# FPGA.net
KiCad netlist of a schematic drawn in Altium Designer
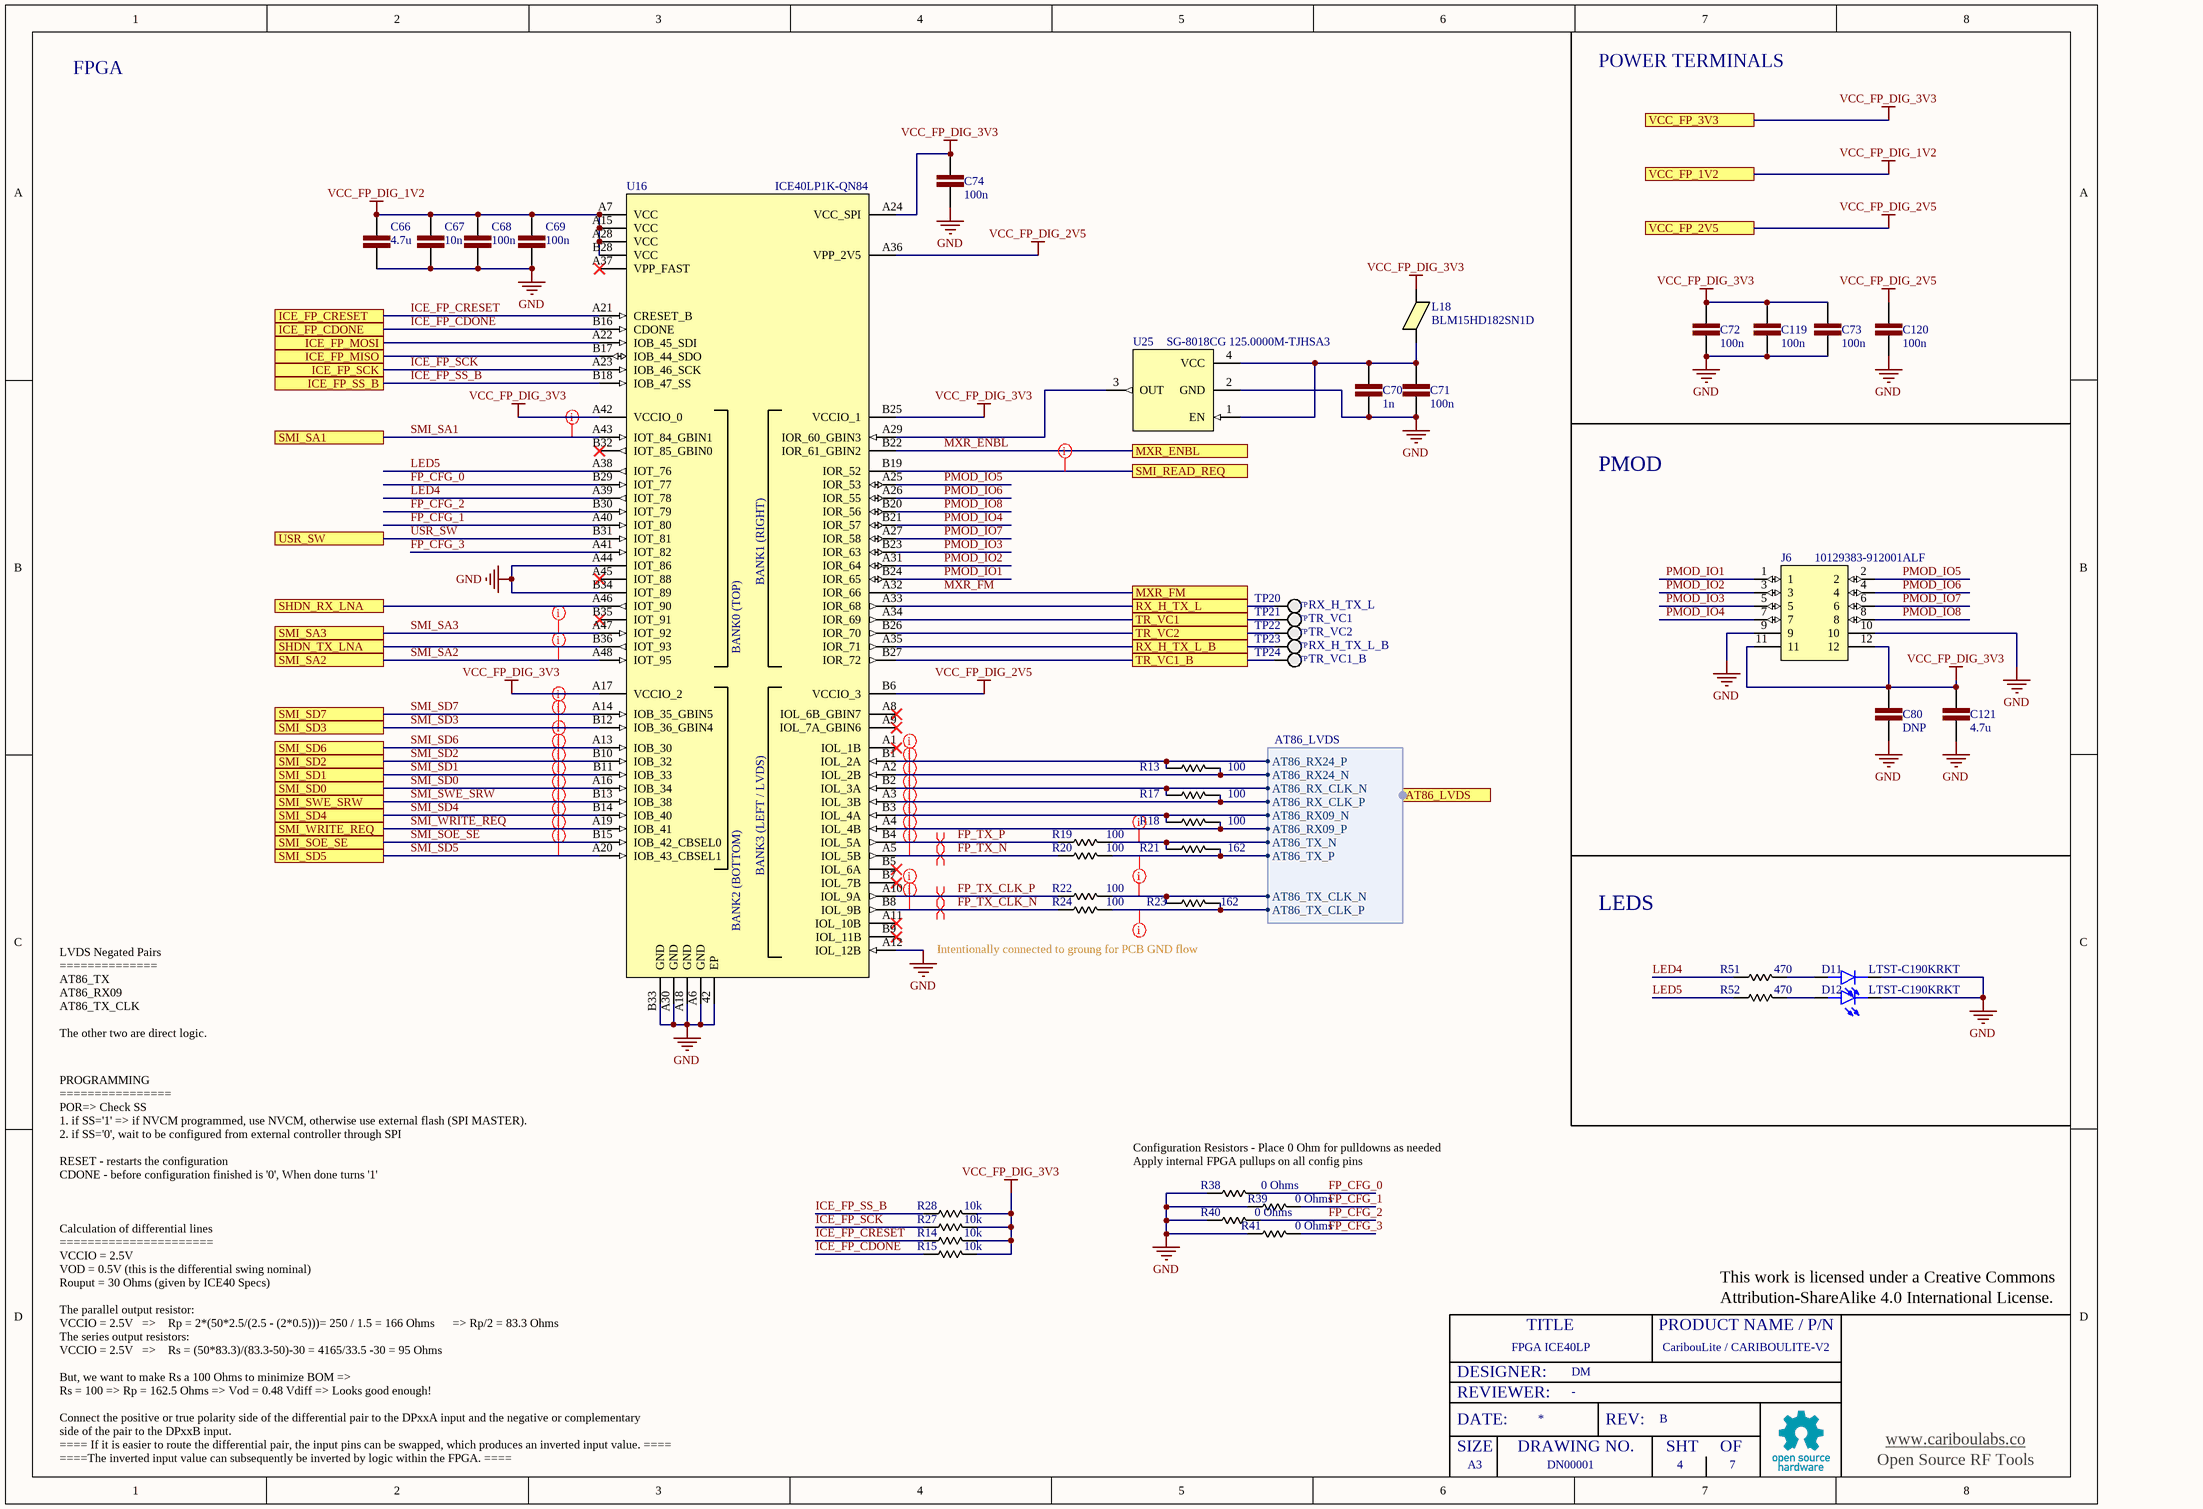
[diagram p0: FPGA.SchDoc]

(export (version "E")
  (design (tool "Eeschema 10.0.6"))
  (components
    (comp (ref "C66")
      (value "4.7u")
      (footprint "MURATA 0402")
      (description "Multilayer Ceramic Capacitors MLCC - SMD/SMT 0402 MLCC X5R 4.7 uF +/ -20% 10V")
      (fields (field (name "TOLERANCE") "20%"))
      (libsource (lib "CuSiP_Lib") (part "Capacitor"))
    )
    (comp (ref "C67")
      (value "10n")
      (footprint "MURATA 0402")
      (description "Multilayer Ceramic Capacitors MLCC - SMD/SMT 0402, 0.01UF 25V C0G")
      (fields (field (name "TOLERANCE") "5%"))
      (libsource (lib "CuSiP_Lib") (part "Capacitor"))
    )
    (comp (ref "C68")
      (value "100n")
      (footprint "MURATA 0402")
      (description "Multilayer Ceramic Capacitors MLCC - SMD/SMT 16V .1uF X5R 0402 10%")
      (fields (field (name "TOLERANCE") "10%"))
      (libsource (lib "") (part "Capacitor_1"))
    )
    (comp (ref "C69")
      (value "100n")
      (footprint "MURATA 0402")
      (description "Multilayer Ceramic Capacitors MLCC - SMD/SMT 16V .1uF X5R 0402 10%")
      (fields (field (name "TOLERANCE") "10%"))
      (libsource (lib "") (part "Capacitor_1"))
    )
    (comp (ref "C70")
      (value "1n")
      (footprint "MURATA 0402")
      (description "Multilayer Ceramic Capacitors MLCC 1000pF ±5% 100V C0G 0402")
      (fields (field (name "TOLERANCE") "5%"))
      (libsource (lib "") (part "Capacitor_2"))
    )
    (comp (ref "C71")
      (value "100n")
      (footprint "MURATA 0402")
      (description "Multilayer Ceramic Capacitors MLCC - SMD/SMT 16V .1uF X5R 0402 10%")
      (fields (field (name "TOLERANCE") "10%"))
      (libsource (lib "") (part "Capacitor_2"))
    )
    (comp (ref "C72")
      (value "100n")
      (footprint "MURATA 0402")
      (description "Multilayer Ceramic Capacitors MLCC - SMD/SMT 16V .1uF X5R 0402 10%")
      (fields (field (name "TOLERANCE") "10%"))
      (libsource (lib "CuSiP_Lib") (part "Capacitor"))
    )
    (comp (ref "C73")
      (value "100n")
      (footprint "MURATA 0402")
      (description "Multilayer Ceramic Capacitors MLCC - SMD/SMT 16V .1uF X5R 0402 10%")
      (fields (field (name "TOLERANCE") "10%"))
      (libsource (lib "") (part "Capacitor_1"))
    )
    (comp (ref "C74")
      (value "100n")
      (footprint "MURATA 0402")
      (description "Multilayer Ceramic Capacitors MLCC - SMD/SMT 16V .1uF X5R 0402 10%")
      (fields (field (name "TOLERANCE") "10%"))
      (libsource (lib "") (part "Capacitor_1"))
    )
    (comp (ref "C80")
      (value "DNP")
      (footprint "MURATA 0402")
      (description "Multilayer Ceramic Capacitors MLCC - SMD/SMT 0402 MLCC X5R 4.7 uF +/ -20% 10V")
      (fields (field (name "TOLERANCE") "20%"))
      (libsource (lib "CuSiP_Lib") (part "Capacitor"))
    )
    (comp (ref "C119")
      (value "100n")
      (footprint "MURATA 0402")
      (description "Multilayer Ceramic Capacitors MLCC - SMD/SMT 16V .1uF X5R 0402 10%")
      (fields (field (name "TOLERANCE") "10%"))
      (libsource (lib "CuSiP_Lib") (part "Capacitor"))
    )
    (comp (ref "C120")
      (value "100n")
      (footprint "MURATA 0402")
      (description "Multilayer Ceramic Capacitors MLCC - SMD/SMT 16V .1uF X5R 0402 10%")
      (fields (field (name "TOLERANCE") "10%"))
      (libsource (lib "") (part "Capacitor_1"))
    )
    (comp (ref "C121")
      (value "4.7u")
      (footprint "MURATA 0402")
      (description "Multilayer Ceramic Capacitors MLCC - SMD/SMT 0402 MLCC X5R 4.7 uF +/ -20% 10V")
      (fields (field (name "TOLERANCE") "20%"))
      (libsource (lib "CuSiP_Lib") (part "Capacitor"))
    )
    (comp (ref "D11")
      (value "LTST-C190KRKT")
      (footprint "LEDC1608X35N")
      (description "Red 631nm LED Indication - Discrete 2V 0603")
      (fields (field (name "MANU. P/N") "LTST-C190KRKT"))
      (libsource (lib "CuSiP_Lib") (part "LTST-C190KRKT"))
    )
    (comp (ref "D12")
      (value "LTST-C190KRKT")
      (footprint "LEDC1608X35N")
      (description "Red 631nm LED Indication - Discrete 2V 0603")
      (fields (field (name "MANU. P/N") "LTST-C190KRKT"))
      (libsource (lib "CuSiP_Lib") (part "LTST-C190KRKT"))
    )
    (comp (ref "J6")
      (value "10129383-912001ALF")
      (footprint "10129383912001ALF")
      (description "Headers & Wire Housings ECONOSTIK HEADER DR VT SMT 2X6")
      (fields (field (name "MANU. P/N") "10129383-912001ALF"))
      (libsource (lib "CuSiP_Lib") (part "10129383-912001ALF"))
    )
    (comp (ref "L18")
      (value "BLM15HD182SN1D")
      (footprint "0402 FERRITE BEAD")
      (description "Ferrite Beads 1800ohms GHz HiSpd")
      (fields (field (name "TOLERANCE") "25%") (field (name "MANU. P/N") "BLM15HD182SN1D"))
      (libsource (lib "CuSiP_Lib") (part "BLM15"))
    )
    (comp (ref "R13")
      (value "100")
      (footprint "PANASONIC 0402")
      (description "Thick Film Resistors - SMD 1/16watt 100ohms 1%")
      (fields (field (name "TOLERANCE") "1%"))
      (libsource (lib "CuSiP_Lib") (part "Resistor"))
    )
    (comp (ref "R14")
      (value "10k")
      (footprint "PANASONIC 0402")
      (description "Thick Film Resistors - SMD 0402 1/16watt 10Kohms 1%")
      (fields (field (name "TOLERANCE") "1%"))
      (libsource (lib "CuSiP_Lib") (part "Resistor"))
    )
    (comp (ref "R15")
      (value "10k")
      (footprint "PANASONIC 0402")
      (description "Thick Film Resistors - SMD 0402 1/16watt 10Kohms 1%")
      (fields (field (name "TOLERANCE") "1%"))
      (libsource (lib "CuSiP_Lib") (part "Resistor"))
    )
    (comp (ref "R17")
      (value "100")
      (footprint "PANASONIC 0402")
      (description "Thick Film Resistors - SMD 1/16watt 100ohms 1%")
      (fields (field (name "TOLERANCE") "1%"))
      (libsource (lib "CuSiP_Lib") (part "Resistor"))
    )
    (comp (ref "R18")
      (value "100")
      (footprint "PANASONIC 0402")
      (description "Thick Film Resistors - SMD 1/16watt 100ohms 1%")
      (fields (field (name "TOLERANCE") "1%"))
      (libsource (lib "CuSiP_Lib") (part "Resistor"))
    )
    (comp (ref "R19")
      (value "100")
      (footprint "PANASONIC 0402")
      (description "Thick Film Resistors - SMD 1/16watt 100ohms 1%")
      (fields (field (name "TOLERANCE") "1%"))
      (libsource (lib "CuSiP_Lib") (part "Resistor"))
    )
    (comp (ref "R20")
      (value "100")
      (footprint "PANASONIC 0402")
      (description "Thick Film Resistors - SMD 1/16watt 100ohms 1%")
      (fields (field (name "TOLERANCE") "1%"))
      (libsource (lib "CuSiP_Lib") (part "Resistor"))
    )
    (comp (ref "R21")
      (value "162")
      (footprint "PANASONIC 0402")
      (description "Thick Film Resistors - SMD 1/16watt 162ohms 1%")
      (fields (field (name "TOLERANCE") "1%"))
      (libsource (lib "CuSiP_Lib") (part "Resistor"))
    )
    (comp (ref "R22")
      (value "100")
      (footprint "PANASONIC 0402")
      (description "Thick Film Resistors - SMD 1/16watt 100ohms 1%")
      (fields (field (name "TOLERANCE") "1%"))
      (libsource (lib "CuSiP_Lib") (part "Resistor"))
    )
    (comp (ref "R23")
      (value "162")
      (footprint "PANASONIC 0402")
      (description "Thick Film Resistors - SMD 1/16watt 162ohms 1%")
      (fields (field (name "TOLERANCE") "1%"))
      (libsource (lib "CuSiP_Lib") (part "Resistor"))
    )
    (comp (ref "R24")
      (value "100")
      (footprint "PANASONIC 0402")
      (description "Thick Film Resistors - SMD 1/16watt 100ohms 1%")
      (fields (field (name "TOLERANCE") "1%"))
      (libsource (lib "CuSiP_Lib") (part "Resistor"))
    )
    (comp (ref "R27")
      (value "10k")
      (footprint "PANASONIC 0402")
      (description "Thick Film Resistors - SMD 0402 1/16watt 10Kohms 1%")
      (fields (field (name "TOLERANCE") "1%"))
      (libsource (lib "CuSiP_Lib") (part "Resistor"))
    )
    (comp (ref "R28")
      (value "10k")
      (footprint "PANASONIC 0402")
      (description "Thick Film Resistors - SMD 0402 1/16watt 10Kohms 1%")
      (fields (field (name "TOLERANCE") "1%"))
      (libsource (lib "CuSiP_Lib") (part "Resistor"))
    )
    (comp (ref "R38")
      (value "0 Ohms")
      (footprint "PANASONIC 0402")
      (description "Resistor")
      (fields (field (name "TOLERANCE") "1%"))
      (libsource (lib "") (part "Resistor_1"))
    )
    (comp (ref "R39")
      (value "0 Ohms")
      (footprint "PANASONIC 0402")
      (description "Resistor")
      (fields (field (name "TOLERANCE") "1%"))
      (libsource (lib "") (part "Resistor_1"))
    )
    (comp (ref "R40")
      (value "0 Ohms")
      (footprint "PANASONIC 0402")
      (description "Resistor")
      (fields (field (name "TOLERANCE") "1%"))
      (libsource (lib "") (part "Resistor_1"))
    )
    (comp (ref "R41")
      (value "0 Ohms")
      (footprint "PANASONIC 0402")
      (description "Resistor")
      (fields (field (name "TOLERANCE") "1%"))
      (libsource (lib "") (part "Resistor_1"))
    )
    (comp (ref "R51")
      (value "470")
      (footprint "PANASONIC 0402")
      (description "Thick Film Resistors - SMD 1/16watt 470ohms 1%")
      (fields (field (name "TOLERANCE") "1%"))
      (libsource (lib "CuSiP_Lib") (part "Resistor"))
    )
    (comp (ref "R52")
      (value "470")
      (footprint "PANASONIC 0402")
      (description "Thick Film Resistors - SMD 1/16watt 470ohms 1%")
      (fields (field (name "TOLERANCE") "1%"))
      (libsource (lib "CuSiP_Lib") (part "Resistor"))
    )
    (comp (ref "TP20")
      (value "RX_H_TX_L")
      (footprint "TP_40")
      (libsource (lib "CuSiP_Lib") (part "TEST_POINT"))
    )
    (comp (ref "TP21") (value "TR_VC1") (footprint "TP_40") (libsource (lib "CuSiP_Lib") (part "TEST_POINT")))
    (comp (ref "TP22") (value "TR_VC2") (footprint "TP_40") (libsource (lib "CuSiP_Lib") (part "TEST_POINT")))
    (comp (ref "TP23")
      (value "RX_H_TX_L_B")
      (footprint "TP_40")
      (libsource (lib "CuSiP_Lib") (part "TEST_POINT"))
    )
    (comp (ref "TP24")
      (value "TR_VC1_B")
      (footprint "TP_40")
      (libsource (lib "CuSiP_Lib") (part "TEST_POINT"))
    )
    (comp (ref "U16")
      (value "ICE40LP1K-QN84")
      (footprint "LATTICE_ICE40LP1K-QN84")
      (description "FPGA - Field Programmable Gate Array iCE40LP 1280 LUTs 1.2V Ultra Low-Power")
      (fields (field (name "MANU. P/N") "ICE40LP1K-QN84"))
      (libsource (lib "CuSiP_Lib") (part "ICE40LP1K-QN84"))
    )
    (comp (ref "U25")
      (value "SG-8018CG 125.0000M-TJHPA3")
      (footprint "SG-8018CG")
      (fields (field (name "MANU. P/N") "SG-8018CG 125.0000M-TJHSA3"))
      (libsource (lib "CuSiP_Lib") (part "SG-8018CG 125.0000M-TJHPA3"))
    )
  )
  (nets
    (net (code "2") (name "/FP_CFG_0") (class "Default")
      (node (ref "R38") (pin "1") (pinfunction "1_1") (pintype "passive"))
      (node (ref "U16") (pin "B29") (pinfunction "IOT_77_B29") (pintype "input"))
    )
    (net (code "3") (name "/FP_CFG_1") (class "Default")
      (node (ref "R39") (pin "1") (pinfunction "1_1") (pintype "passive"))
      (node (ref "U16") (pin "A40") (pinfunction "IOT_80_A40") (pintype "input"))
    )
    (net (code "4") (name "/FP_CFG_2") (class "Default")
      (node (ref "R40") (pin "1") (pinfunction "1_1") (pintype "passive"))
      (node (ref "U16") (pin "B30") (pinfunction "IOT_79_B30") (pintype "input"))
    )
    (net (code "5") (name "/FP_CFG_3") (class "Default")
      (node (ref "R41") (pin "1") (pinfunction "1_1") (pintype "passive"))
      (node (ref "U16") (pin "A41") (pinfunction "IOT_82_A41") (pintype "input"))
    )
    (net (code "6") (name "/FP_TX_CLK_N") (class "Default")
      (node (ref "R24") (pin "1") (pinfunction "1_1") (pintype "passive"))
      (node (ref "U16") (pin "B8") (pinfunction "IOL_9B_B8") (pintype "output"))
    )
    (net (code "7") (name "/FP_TX_CLK_P") (class "Default")
      (node (ref "R22") (pin "1") (pinfunction "1_1") (pintype "passive"))
      (node (ref "U16") (pin "A10") (pinfunction "IOL_9A_A10") (pintype "output"))
    )
    (net (code "8") (name "/FP_TX_N") (class "Default")
      (node (ref "R20") (pin "1") (pinfunction "1_1") (pintype "passive"))
      (node (ref "U16") (pin "A5") (pinfunction "IOL_5B_A5") (pintype "output"))
    )
    (net (code "9") (name "/FP_TX_P") (class "Default")
      (node (ref "R19") (pin "1") (pinfunction "1_1") (pintype "passive"))
      (node (ref "U16") (pin "B4") (pinfunction "IOL_5A_B4") (pintype "output"))
    )
    (net (code "10") (name "/ICE_FP_CDONE") (class "Default")
      (node (ref "R15") (pin "1") (pinfunction "1_1") (pintype "passive"))
      (node (ref "U16") (pin "B16") (pinfunction "CDONE_B16") (pintype "input"))
    )
    (net (code "11") (name "/ICE_FP_CRESET") (class "Default")
      (node (ref "R14") (pin "1") (pinfunction "1_1") (pintype "passive"))
      (node (ref "U16") (pin "A21") (pinfunction "CRESET_B_A21") (pintype "input"))
    )
    (net (code "12") (name "/ICE_FP_MISO") (class "Default")
      (node (ref "U16") (pin "B17") (pinfunction "IOB_44_SDO_B17") (pintype "bidirectional"))
    )
    (net (code "13") (name "/ICE_FP_MOSI") (class "Default")
      (node (ref "U16") (pin "A22") (pinfunction "IOB_45_SDI_A22") (pintype "input"))
    )
    (net (code "14") (name "/ICE_FP_SCK") (class "Default")
      (node (ref "R27") (pin "1") (pinfunction "1_1") (pintype "passive"))
      (node (ref "U16") (pin "A23") (pinfunction "IOB_46_SCK_A23") (pintype "input"))
    )
    (net (code "15") (name "/ICE_FP_SS_B") (class "Default")
      (node (ref "R28") (pin "1") (pinfunction "1_1") (pintype "passive"))
      (node (ref "U16") (pin "B18") (pinfunction "IOB_47_SS_B18") (pintype "input"))
    )
    (net (code "16") (name "/LED4") (class "Default")
      (node (ref "R51") (pin "1") (pinfunction "1_1") (pintype "passive"))
      (node (ref "U16") (pin "A39") (pinfunction "IOT_78_A39") (pintype "output"))
    )
    (net (code "17") (name "/LED5") (class "Default")
      (node (ref "R52") (pin "1") (pinfunction "1_1") (pintype "passive"))
      (node (ref "U16") (pin "A38") (pinfunction "IOT_76_A38") (pintype "output"))
    )
    (net (code "18") (name "/MXR_ENBL") (class "Default")
      (node (ref "U16") (pin "B22") (pinfunction "IOR_61_GBIN2_B22") (pintype "passive"))
    )
    (net (code "19") (name "/MXR_FM") (class "Default")
      (node (ref "U16") (pin "A32") (pinfunction "IOR_66_A32") (pintype "passive"))
    )
    (net (code "20") (name "/PMOD_IO1") (class "Default")
      (node (ref "J6") (pin "1") (pinfunction "1_1") (pintype "bidirectional"))
      (node (ref "U16") (pin "B24") (pinfunction "IOR_65_B24") (pintype "bidirectional"))
    )
    (net (code "21") (name "/PMOD_IO2") (class "Default")
      (node (ref "J6") (pin "3") (pinfunction "3_3") (pintype "bidirectional"))
      (node (ref "U16") (pin "A31") (pinfunction "IOR_64_A31") (pintype "bidirectional"))
    )
    (net (code "22") (name "/PMOD_IO3") (class "Default")
      (node (ref "J6") (pin "5") (pinfunction "5_5") (pintype "bidirectional"))
      (node (ref "U16") (pin "B23") (pinfunction "IOR_63_B23") (pintype "bidirectional"))
    )
    (net (code "23") (name "/PMOD_IO4") (class "Default")
      (node (ref "J6") (pin "7") (pinfunction "7_7") (pintype "bidirectional"))
      (node (ref "U16") (pin "B21") (pinfunction "IOR_57_B21") (pintype "bidirectional"))
    )
    (net (code "24") (name "/PMOD_IO5") (class "Default")
      (node (ref "J6") (pin "2") (pinfunction "2_2") (pintype "bidirectional"))
      (node (ref "U16") (pin "A25") (pinfunction "IOR_53_A25") (pintype "bidirectional"))
    )
    (net (code "25") (name "/PMOD_IO6") (class "Default")
      (node (ref "J6") (pin "4") (pinfunction "4_4") (pintype "bidirectional"))
      (node (ref "U16") (pin "A26") (pinfunction "IOR_55_A26") (pintype "bidirectional"))
    )
    (net (code "26") (name "/PMOD_IO7") (class "Default")
      (node (ref "J6") (pin "6") (pinfunction "6_6") (pintype "bidirectional"))
      (node (ref "U16") (pin "A27") (pinfunction "IOR_58_A27") (pintype "bidirectional"))
    )
    (net (code "27") (name "/PMOD_IO8") (class "Default")
      (node (ref "J6") (pin "8") (pinfunction "8_8") (pintype "bidirectional"))
      (node (ref "U16") (pin "B20") (pinfunction "IOR_56_B20") (pintype "bidirectional"))
    )
    (net (code "28") (name "/RX_H_TX_L") (class "Default")
      (node (ref "TP20") (pin "1") (pinfunction "TP_1") (pintype "passive"))
      (node (ref "U16") (pin "A33") (pinfunction "IOR_68_A33") (pintype "output"))
    )
    (net (code "29") (name "/RX_H_TX_L_B") (class "Default")
      (node (ref "TP23") (pin "1") (pinfunction "TP_1") (pintype "passive"))
      (node (ref "U16") (pin "A35") (pinfunction "IOR_71_A35") (pintype "output"))
    )
    (net (code "30") (name "/SHDN_RX_LNA") (class "Default")
      (node (ref "U16") (pin "A46") (pinfunction "IOT_90_A46") (pintype "output"))
    )
    (net (code "31") (name "/SHDN_TX_LNA") (class "Default")
      (node (ref "U16") (pin "B36") (pinfunction "IOT_93_B36") (pintype "output"))
    )
    (net (code "32") (name "/SMI_READ_REQ") (class "Default")
      (node (ref "U16") (pin "B19") (pinfunction "IOR_52_B19") (pintype "passive"))
    )
    (net (code "33") (name "/SMI_SA1") (class "Default")
      (node (ref "U16") (pin "A43") (pinfunction "IOT_84_GBIN1_A43") (pintype "input"))
    )
    (net (code "34") (name "/SMI_SA2") (class "Default")
      (node (ref "U16") (pin "A48") (pinfunction "IOT_95_A48") (pintype "input"))
    )
    (net (code "35") (name "/SMI_SA3") (class "Default")
      (node (ref "U16") (pin "A47") (pinfunction "IOT_92_A47") (pintype "input"))
    )
    (net (code "36") (name "/SMI_SD0") (class "Default")
      (node (ref "U16") (pin "A16") (pinfunction "IOB_34_A16") (pintype "input"))
    )
    (net (code "37") (name "/SMI_SD1") (class "Default")
      (node (ref "U16") (pin "B11") (pinfunction "IOB_33_B11") (pintype "input"))
    )
    (net (code "38") (name "/SMI_SD2") (class "Default")
      (node (ref "U16") (pin "B10") (pinfunction "IOB_32_B10") (pintype "input"))
    )
    (net (code "39") (name "/SMI_SD3") (class "Default")
      (node (ref "U16") (pin "B12") (pinfunction "IOB_36_GBIN4_B12") (pintype "input"))
    )
    (net (code "40") (name "/SMI_SD4") (class "Default")
      (node (ref "U16") (pin "B14") (pinfunction "IOB_40_B14") (pintype "input"))
    )
    (net (code "41") (name "/SMI_SD5") (class "Default")
      (node (ref "U16") (pin "A20") (pinfunction "IOB_43_CBSEL1_A20") (pintype "input"))
    )
    (net (code "42") (name "/SMI_SD6") (class "Default")
      (node (ref "U16") (pin "A13") (pinfunction "IOB_30_A13") (pintype "input"))
    )
    (net (code "43") (name "/SMI_SD7") (class "Default")
      (node (ref "U16") (pin "A14") (pinfunction "IOB_35_GBIN5_A14") (pintype "input"))
    )
    (net (code "44") (name "/SMI_SOE_SE") (class "Default")
      (node (ref "U16") (pin "B15") (pinfunction "IOB_42_CBSEL0_B15") (pintype "input"))
    )
    (net (code "45") (name "/SMI_SWE_SRW") (class "Default")
      (node (ref "U16") (pin "B13") (pinfunction "IOB_38_B13") (pintype "input"))
    )
    (net (code "46") (name "/SMI_WRITE_REQ") (class "Default")
      (node (ref "U16") (pin "A19") (pinfunction "IOB_41_A19") (pintype "input"))
    )
    (net (code "47") (name "/TR_VC1") (class "Default")
      (node (ref "TP21") (pin "1") (pinfunction "TP_1") (pintype "passive"))
      (node (ref "U16") (pin "A34") (pinfunction "IOR_69_A34") (pintype "output"))
    )
    (net (code "48") (name "/TR_VC1_B") (class "Default")
      (node (ref "TP24") (pin "1") (pinfunction "TP_1") (pintype "passive"))
      (node (ref "U16") (pin "B27") (pinfunction "IOR_72_B27") (pintype "output"))
    )
    (net (code "49") (name "/TR_VC2") (class "Default")
      (node (ref "TP22") (pin "1") (pinfunction "TP_1") (pintype "passive"))
      (node (ref "U16") (pin "B26") (pinfunction "IOR_70_B26") (pintype "output"))
    )
    (net (code "50") (name "/USR_SW") (class "Default")
      (node (ref "U16") (pin "B31") (pinfunction "IOT_81_B31") (pintype "input"))
    )
    (net (code "52") (name "GND") (class "Default")
      (node (ref "C119") (pin "2") (pinfunction "2_2") (pintype "passive"))
      (node (ref "C120") (pin "1") (pinfunction "1_1") (pintype "passive"))
      (node (ref "C121") (pin "2") (pinfunction "2_2") (pintype "passive"))
      (node (ref "C66") (pin "2") (pinfunction "2_2") (pintype "passive"))
      (node (ref "C67") (pin "2") (pinfunction "2_2") (pintype "passive"))
      (node (ref "C68") (pin "1") (pinfunction "1_1") (pintype "passive"))
      (node (ref "C69") (pin "1") (pinfunction "1_1") (pintype "passive"))
      (node (ref "C70") (pin "1") (pinfunction "1_1") (pintype "passive"))
      (node (ref "C71") (pin "1") (pinfunction "1_1") (pintype "passive"))
      (node (ref "C72") (pin "2") (pinfunction "2_2") (pintype "passive"))
      (node (ref "C73") (pin "1") (pinfunction "1_1") (pintype "passive"))
      (node (ref "C74") (pin "1") (pinfunction "1_1") (pintype "passive"))
      (node (ref "C80") (pin "2") (pinfunction "2_2") (pintype "passive"))
      (node (ref "D11") (pin "C") (pinfunction "C_C") (pintype "passive"))
      (node (ref "D12") (pin "C") (pinfunction "C_C") (pintype "passive"))
      (node (ref "J6") (pin "10") (pinfunction "10_10") (pintype "power_in"))
      (node (ref "J6") (pin "9") (pinfunction "9_9") (pintype "power_in"))
      (node (ref "R38") (pin "2") (pinfunction "2_2") (pintype "passive"))
      (node (ref "R39") (pin "2") (pinfunction "2_2") (pintype "passive"))
      (node (ref "R40") (pin "2") (pinfunction "2_2") (pintype "passive"))
      (node (ref "R41") (pin "2") (pinfunction "2_2") (pintype "passive"))
      (node (ref "U16") (pin "42") (pinfunction "EP_42") (pintype "power_in"))
      (node (ref "U16") (pin "A12") (pinfunction "IOL_12B_A12") (pintype "input"))
      (node (ref "U16") (pin "A18") (pinfunction "GND_A18") (pintype "power_in"))
      (node (ref "U16") (pin "A30") (pinfunction "GND_A30") (pintype "power_in"))
      (node (ref "U16") (pin "A44") (pinfunction "IOT_86_A44") (pintype "passive"))
      (node (ref "U16") (pin "A6") (pinfunction "GND_A6") (pintype "power_in"))
      (node (ref "U16") (pin "B33") (pinfunction "GND_B33") (pintype "power_in"))
      (node (ref "U16") (pin "B34") (pinfunction "IOT_89_B34") (pintype "passive"))
      (node (ref "U25") (pin "2") (pinfunction "GND_2") (pintype "power_in"))
    )
    (net (code "53") (name "Net-(D11-PadA)") (class "Default")
      (node (ref "D11") (pin "A") (pinfunction "A_A") (pintype "passive"))
      (node (ref "R51") (pin "2") (pinfunction "2_2") (pintype "passive"))
    )
    (net (code "54") (name "Net-(D12-PadA)") (class "Default")
      (node (ref "D12") (pin "A") (pinfunction "A_A") (pintype "passive"))
      (node (ref "R52") (pin "2") (pinfunction "2_2") (pintype "passive"))
    )
    (net (code "55") (name "Net-(R19-Pad2)") (class "Default")
      (node (ref "R19") (pin "2") (pinfunction "2_2") (pintype "passive"))
      (node (ref "R21") (pin "1") (pinfunction "1_1") (pintype "passive"))
    )
    (net (code "56") (name "Net-(R20-Pad2)") (class "Default")
      (node (ref "R20") (pin "2") (pinfunction "2_2") (pintype "passive"))
      (node (ref "R21") (pin "2") (pinfunction "2_2") (pintype "passive"))
    )
    (net (code "57") (name "Net-(R22-Pad2)") (class "Default")
      (node (ref "R22") (pin "2") (pinfunction "2_2") (pintype "passive"))
      (node (ref "R23") (pin "1") (pinfunction "1_1") (pintype "passive"))
    )
    (net (code "58") (name "Net-(R23-Pad2)") (class "Default")
      (node (ref "R23") (pin "2") (pinfunction "2_2") (pintype "passive"))
      (node (ref "R24") (pin "2") (pinfunction "2_2") (pintype "passive"))
    )
    (net (code "59") (name "Net-(U16-IOL_2A)") (class "Default")
      (node (ref "R13") (pin "1") (pinfunction "1_1") (pintype "passive"))
      (node (ref "U16") (pin "B1") (pinfunction "IOL_2A_B1") (pintype "input"))
    )
    (net (code "60") (name "Net-(U16-IOL_2B)") (class "Default")
      (node (ref "R13") (pin "2") (pinfunction "2_2") (pintype "passive"))
      (node (ref "U16") (pin "A2") (pinfunction "IOL_2B_A2") (pintype "input"))
    )
    (net (code "61") (name "Net-(U16-IOL_3A)") (class "Default")
      (node (ref "R17") (pin "1") (pinfunction "1_1") (pintype "passive"))
      (node (ref "U16") (pin "B2") (pinfunction "IOL_3A_B2") (pintype "input"))
    )
    (net (code "62") (name "Net-(U16-IOL_3B)") (class "Default")
      (node (ref "R17") (pin "2") (pinfunction "2_2") (pintype "passive"))
      (node (ref "U16") (pin "A3") (pinfunction "IOL_3B_A3") (pintype "input"))
    )
    (net (code "63") (name "Net-(U16-IOL_4A)") (class "Default")
      (node (ref "R18") (pin "1") (pinfunction "1_1") (pintype "passive"))
      (node (ref "U16") (pin "B3") (pinfunction "IOL_4A_B3") (pintype "input"))
    )
    (net (code "64") (name "Net-(U16-IOL_4B)") (class "Default")
      (node (ref "R18") (pin "2") (pinfunction "2_2") (pintype "passive"))
      (node (ref "U16") (pin "A4") (pinfunction "IOL_4B_A4") (pintype "input"))
    )
    (net (code "65") (name "Net-(U16-IOR_60_GBIN3)") (class "Default")
      (node (ref "U16") (pin "A29") (pinfunction "IOR_60_GBIN3_A29") (pintype "input"))
      (node (ref "U25") (pin "3") (pinfunction "OUT_3") (pintype "output"))
    )
    (net (code "66") (name "Net-(U25-EN)") (class "Default")
      (node (ref "C70") (pin "2") (pinfunction "2_2") (pintype "passive"))
      (node (ref "C71") (pin "2") (pinfunction "2_2") (pintype "passive"))
      (node (ref "L18") (pin "1") (pinfunction "1_1") (pintype "passive"))
      (node (ref "U25") (pin "1") (pinfunction "EN_1") (pintype "input"))
      (node (ref "U25") (pin "4") (pinfunction "VCC_4") (pintype "power_in"))
    )
    (net (code "67") (name "VCC_FP_DIG_1V2") (class "Default")
      (node (ref "C66") (pin "1") (pinfunction "1_1") (pintype "passive"))
      (node (ref "C67") (pin "1") (pinfunction "1_1") (pintype "passive"))
      (node (ref "C68") (pin "2") (pinfunction "2_2") (pintype "passive"))
      (node (ref "C69") (pin "2") (pinfunction "2_2") (pintype "passive"))
      (node (ref "U16") (pin "A15") (pinfunction "VCC_A15") (pintype "power_in"))
      (node (ref "U16") (pin "A28") (pinfunction "VCC_A28") (pintype "power_in"))
      (node (ref "U16") (pin "A7") (pinfunction "VCC_A7") (pintype "power_in"))
      (node (ref "U16") (pin "B28") (pinfunction "VCC_B28") (pintype "power_in"))
    )
    (net (code "68") (name "VCC_FP_DIG_2V5") (class "Default")
      (node (ref "C120") (pin "2") (pinfunction "2_2") (pintype "passive"))
      (node (ref "U16") (pin "A36") (pinfunction "VPP_2V5_A36") (pintype "power_in"))
      (node (ref "U16") (pin "B6") (pinfunction "VCCIO_3_B6") (pintype "power_in"))
    )
    (net (code "69") (name "VCC_FP_DIG_3V3") (class "Default")
      (node (ref "C119") (pin "1") (pinfunction "1_1") (pintype "passive"))
      (node (ref "C121") (pin "1") (pinfunction "1_1") (pintype "passive"))
      (node (ref "C72") (pin "1") (pinfunction "1_1") (pintype "passive"))
      (node (ref "C73") (pin "2") (pinfunction "2_2") (pintype "passive"))
      (node (ref "C74") (pin "2") (pinfunction "2_2") (pintype "passive"))
      (node (ref "C80") (pin "1") (pinfunction "1_1") (pintype "passive"))
      (node (ref "J6") (pin "11") (pinfunction "11_11") (pintype "power_in"))
      (node (ref "J6") (pin "12") (pinfunction "12_12") (pintype "power_in"))
      (node (ref "L18") (pin "2") (pinfunction "2_2") (pintype "passive"))
      (node (ref "R14") (pin "2") (pinfunction "2_2") (pintype "passive"))
      (node (ref "R15") (pin "2") (pinfunction "2_2") (pintype "passive"))
      (node (ref "R27") (pin "2") (pinfunction "2_2") (pintype "passive"))
      (node (ref "R28") (pin "2") (pinfunction "2_2") (pintype "passive"))
      (node (ref "U16") (pin "A17") (pinfunction "VCCIO_2_A17") (pintype "power_in"))
      (node (ref "U16") (pin "A24") (pinfunction "VCC_SPI_A24") (pintype "power_in"))
      (node (ref "U16") (pin "A42") (pinfunction "VCCIO_0_A42") (pintype "power_in"))
      (node (ref "U16") (pin "B25") (pinfunction "VCCIO_1_B25") (pintype "power_in"))
    )
    (net (code "70") (name "unconnected-(U16-IOL_1B-PadA1)") (class "Default")
      (node (ref "U16") (pin "A1") (pinfunction "IOL_1B_A1") (pintype "passive+no_connect"))
    )
    (net (code "71") (name "unconnected-(U16-IOL_6A-PadB5)") (class "Default")
      (node (ref "U16") (pin "B5") (pinfunction "IOL_6A_B5") (pintype "passive+no_connect"))
    )
    (net (code "72") (name "unconnected-(U16-IOL_6B_GBIN7-PadA8)") (class "Default")
      (node (ref "U16") (pin "A8") (pinfunction "IOL_6B_GBIN7_A8") (pintype "passive+no_connect"))
    )
    (net (code "73") (name "unconnected-(U16-IOL_7A_GBIN6-PadA9)") (class "Default")
      (node (ref "U16") (pin "A9") (pinfunction "IOL_7A_GBIN6_A9") (pintype "passive+no_connect"))
    )
    (net (code "74") (name "unconnected-(U16-IOL_7B-PadB7)") (class "Default")
      (node (ref "U16") (pin "B7") (pinfunction "IOL_7B_B7") (pintype "passive+no_connect"))
    )
    (net (code "75") (name "unconnected-(U16-IOL_10B-PadA11)") (class "Default")
      (node (ref "U16") (pin "A11") (pinfunction "IOL_10B_A11") (pintype "passive+no_connect"))
    )
    (net (code "76") (name "unconnected-(U16-IOL_11B-PadB9)") (class "Default")
      (node (ref "U16") (pin "B9") (pinfunction "IOL_11B_B9") (pintype "passive+no_connect"))
    )
    (net (code "77") (name "unconnected-(U16-IOT_85_GBIN0-PadB32)") (class "Default")
      (node (ref "U16") (pin "B32") (pinfunction "IOT_85_GBIN0_B32") (pintype "output+no_connect"))
    )
    (net (code "78") (name "unconnected-(U16-IOT_88-PadA45)") (class "Default")
      (node (ref "U16") (pin "A45") (pinfunction "IOT_88_A45") (pintype "passive+no_connect"))
    )
    (net (code "79") (name "unconnected-(U16-IOT_91-PadB35)") (class "Default")
      (node (ref "U16") (pin "B35") (pinfunction "IOT_91_B35") (pintype "passive+no_connect"))
    )
    (net (code "80") (name "unconnected-(U16-VPP_FAST-PadA37)") (class "Default")
      (node (ref "U16") (pin "A37") (pinfunction "VPP_FAST_A37") (pintype "passive+no_connect"))
    )
  )
)
